# 1_interface.net
KiCad netlist of a schematic drawn in Altium Designer
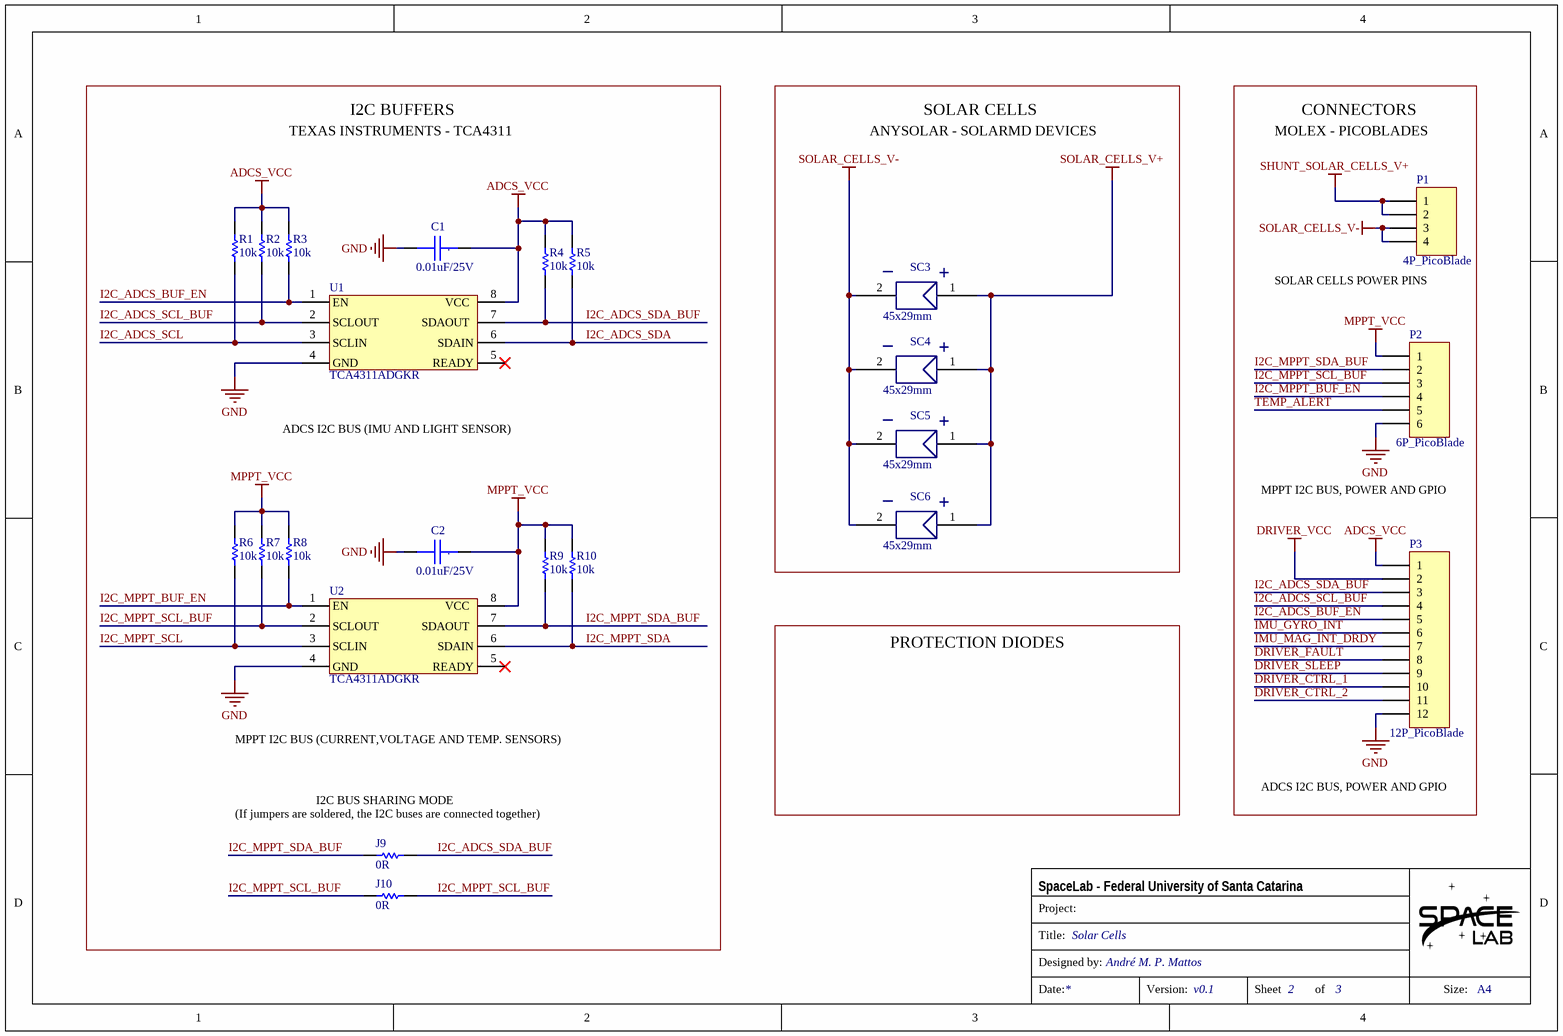
[diagram p0: 1_interface.schdoc]

(export (version "E")
  (design (tool "Eeschema 10.0.6"))
  (components
    (comp (ref "C1")
      (value "0.01uF/25V")
      (footprint "CC0805")
      (description "CAP CER 0.01uF 25V 10% X7R 0805")
      (fields (field (name "PARTNUMBER") "CL21B103KAANNNC"))
      (libsource (lib "schematics_library_legacy") (part "Cap_Cer_X7R_0.01uF_50V_0805"))
    )
    (comp (ref "C2")
      (value "0.01uF/25V")
      (footprint "CC0805")
      (description "CAP CER 0.01uF 25V 10% X7R 0805")
      (fields (field (name "PARTNUMBER") "CL21B103KAANNNC"))
      (libsource (lib "schematics_library_legacy") (part "Cap_Cer_X7R_0.01uF_50V_0805"))
    )
    (comp (ref "J9")
      (value "0R")
      (footprint "0805")
      (description "RES 0R OHM 1/16W JUMPER 0805")
      (fields (field (name "PARTNUMBER") "CRCW08050000Z0EA"))
      (libsource (lib "schematics_library_legacy") (part "R0R_JUMPER_1/16W_0805"))
    )
    (comp (ref "J10")
      (value "0R")
      (footprint "0805")
      (description "RES 0R OHM 1/16W JUMPER 0805")
      (fields (field (name "PARTNUMBER") "CRCW08050000Z0EA"))
      (libsource (lib "schematics_library_legacy") (part "R0R_JUMPER_1/16W_0805"))
    )
    (comp (ref "P1")
      (value "4P_PicoBlade")
      (footprint "HDR4 PicoBlade")
      (description "Header, 4-Pin")
      (fields
        (field (name "PARTNUMBER") "53398-0471")
        (field (name "MANUFACTURER") "Molex")
        (field (name "PUBLISHER") "Altium Limited")
      )
      (libsource (lib "schematics_library_legacy") (part "Header 4_PicoBlade"))
    )
    (comp (ref "P2")
      (value "6P_PicoBlade")
      (footprint "HDR6 PicoBlade")
      (description "Header, 6-Pin, Right Angle")
      (fields (field (name "PARTNUMBER") "53398-0671") (field (name "PUBLISHER") "Altium Limited"))
      (libsource (lib "schematics_library_legacy") (part "Header 6H_PicoBlade"))
    )
    (comp (ref "P3")
      (value "12P_PicoBlade")
      (footprint "HDR12 PicoBlade - duplicate")
      (description "Header, 12-Pin")
      (fields (field (name "PARTNUMBER") "53398-1271") (field (name "PUBLISHER") "Altium Limited"))
      (libsource (lib "schematics_library_legacy") (part "Header 12_PicoBlade"))
    )
    (comp (ref "R1")
      (value "10k")
      (footprint "0805")
      (description "RES 10K OHM 1/8W 1%  0805")
      (fields (field (name "PARTNUMBER") "CRCW080510K0FKEA"))
      (libsource (lib "schematics_library_legacy") (part "R10k_1%_1/8W_0805"))
    )
    (comp (ref "R2")
      (value "10k")
      (footprint "0805")
      (description "RES 10K OHM 1/8W 1%  0805")
      (fields (field (name "PARTNUMBER") "CRCW080510K0FKEA"))
      (libsource (lib "schematics_library_legacy") (part "R10k_1%_1/8W_0805"))
    )
    (comp (ref "R3")
      (value "10k")
      (footprint "0805")
      (description "RES 10K OHM 1/8W 1%  0805")
      (fields (field (name "PARTNUMBER") "CRCW080510K0FKEA"))
      (libsource (lib "schematics_library_legacy") (part "R10k_1%_1/8W_0805"))
    )
    (comp (ref "R4")
      (value "10k")
      (footprint "0805")
      (description "RES 10K OHM 1/8W 1%  0805")
      (fields (field (name "PARTNUMBER") "CRCW080510K0FKEA"))
      (libsource (lib "schematics_library_legacy") (part "R10k_1%_1/8W_0805"))
    )
    (comp (ref "R5")
      (value "10k")
      (footprint "0805")
      (description "RES 10K OHM 1/8W 1%  0805")
      (fields (field (name "PARTNUMBER") "CRCW080510K0FKEA"))
      (libsource (lib "schematics_library_legacy") (part "R10k_1%_1/8W_0805"))
    )
    (comp (ref "R6")
      (value "10k")
      (footprint "0805")
      (description "RES 10K OHM 1/8W 1%  0805")
      (fields (field (name "PARTNUMBER") "CRCW080510K0FKEA"))
      (libsource (lib "schematics_library_legacy") (part "R10k_1%_1/8W_0805"))
    )
    (comp (ref "R7")
      (value "10k")
      (footprint "0805")
      (description "RES 10K OHM 1/8W 1%  0805")
      (fields (field (name "PARTNUMBER") "CRCW080510K0FKEA"))
      (libsource (lib "schematics_library_legacy") (part "R10k_1%_1/8W_0805"))
    )
    (comp (ref "R8")
      (value "10k")
      (footprint "0805")
      (description "RES 10K OHM 1/8W 1%  0805")
      (fields (field (name "PARTNUMBER") "CRCW080510K0FKEA"))
      (libsource (lib "schematics_library_legacy") (part "R10k_1%_1/8W_0805"))
    )
    (comp (ref "R9")
      (value "10k")
      (footprint "0805")
      (description "RES 10K OHM 1/8W 1%  0805")
      (fields (field (name "PARTNUMBER") "CRCW080510K0FKEA"))
      (libsource (lib "schematics_library_legacy") (part "R10k_1%_1/8W_0805"))
    )
    (comp (ref "R10")
      (value "10k")
      (footprint "0805")
      (description "RES 10K OHM 1/8W 1%  0805")
      (fields (field (name "PARTNUMBER") "CRCW080510K0FKEA"))
      (libsource (lib "schematics_library_legacy") (part "R10k_1%_1/8W_0805"))
    )
    (comp (ref "SC3")
      (value "SC")
      (footprint "45x29mm_cell")
      (description "sm141k08lv")
      (fields (field (name "SIZE") "45x29mm"))
      (libsource (lib "schematics_library_legacy") (part "solar_cell_sm141k08lv"))
    )
    (comp (ref "SC4")
      (value "SC")
      (footprint "45x29mm_cell")
      (description "sm141k08lv")
      (fields (field (name "SIZE") "45x29mm"))
      (libsource (lib "schematics_library_legacy") (part "solar_cell_sm141k08lv"))
    )
    (comp (ref "SC5")
      (value "SC")
      (footprint "45x29mm_cell")
      (description "sm141k08lv")
      (fields (field (name "SIZE") "45x29mm"))
      (libsource (lib "schematics_library_legacy") (part "solar_cell_sm141k08lv"))
    )
    (comp (ref "SC6")
      (value "SC")
      (footprint "45x29mm_cell")
      (description "sm141k08lv")
      (fields (field (name "SIZE") "45x29mm"))
      (libsource (lib "schematics_library_legacy") (part "solar_cell_sm141k08lv"))
    )
    (comp (ref "U1")
      (value "TCA4311ADGKR")
      (footprint "DGK8")
      (description "IC SIGNAL BUFFER I2C VSSOP-8")
      (libsource (lib "schematics_library_legacy") (part "TCA4311ADGKR"))
    )
    (comp (ref "U2")
      (value "TCA4311ADGKR")
      (footprint "DGK8")
      (description "IC SIGNAL BUFFER I2C VSSOP-8")
      (libsource (lib "schematics_library_legacy") (part "TCA4311ADGKR"))
    )
  )
  (nets
    (net (code "1") (name "/DRIVER_CTRL_1") (class "Default")
      (node (ref "P3") (pin "10") (pinfunction "10_10") (pintype "passive"))
    )
    (net (code "2") (name "/DRIVER_CTRL_2") (class "Default")
      (node (ref "P3") (pin "11") (pinfunction "11_11") (pintype "passive"))
    )
    (net (code "3") (name "/DRIVER_FAULT") (class "Default")
      (node (ref "P3") (pin "8") (pinfunction "8_8") (pintype "passive"))
    )
    (net (code "4") (name "/DRIVER_SLEEP") (class "Default")
      (node (ref "P3") (pin "9") (pinfunction "9_9") (pintype "passive"))
    )
    (net (code "5") (name "/I2C_ADCS_BUF_EN") (class "Default")
      (node (ref "P3") (pin "5") (pinfunction "5_5") (pintype "passive"))
      (node (ref "R3") (pin "1") (pinfunction "1_1") (pintype "passive"))
      (node (ref "U1") (pin "1") (pinfunction "EN_1") (pintype "passive"))
    )
    (net (code "6") (name "/I2C_ADCS_SCL") (class "Default")
      (node (ref "R1") (pin "1") (pinfunction "1_1") (pintype "passive"))
      (node (ref "U1") (pin "3") (pinfunction "SCLIN_3") (pintype "passive"))
    )
    (net (code "7") (name "/I2C_ADCS_SCL_BUF") (class "Default")
      (node (ref "P3") (pin "4") (pinfunction "4_4") (pintype "passive"))
      (node (ref "R2") (pin "1") (pinfunction "1_1") (pintype "passive"))
      (node (ref "U1") (pin "2") (pinfunction "SCLOUT_2") (pintype "passive"))
    )
    (net (code "8") (name "/I2C_ADCS_SDA") (class "Default")
      (node (ref "R5") (pin "1") (pinfunction "1_1") (pintype "passive"))
      (node (ref "U1") (pin "6") (pinfunction "SDAIN_6") (pintype "passive"))
    )
    (net (code "9") (name "/I2C_ADCS_SDA_BUF") (class "Default")
      (node (ref "J9") (pin "1") (pinfunction "1_1") (pintype "passive"))
      (node (ref "P3") (pin "3") (pinfunction "3_3") (pintype "passive"))
      (node (ref "R4") (pin "1") (pinfunction "1_1") (pintype "passive"))
      (node (ref "U1") (pin "7") (pinfunction "SDAOUT_7") (pintype "passive"))
    )
    (net (code "10") (name "/I2C_MPPT_BUF_EN") (class "Default")
      (node (ref "P2") (pin "4") (pinfunction "4_4") (pintype "passive"))
      (node (ref "R8") (pin "1") (pinfunction "1_1") (pintype "passive"))
      (node (ref "U2") (pin "1") (pinfunction "EN_1") (pintype "passive"))
    )
    (net (code "11") (name "/I2C_MPPT_SCL") (class "Default")
      (node (ref "R6") (pin "1") (pinfunction "1_1") (pintype "passive"))
      (node (ref "U2") (pin "3") (pinfunction "SCLIN_3") (pintype "passive"))
    )
    (net (code "12") (name "/I2C_MPPT_SCL_BUF") (class "Default")
      (node (ref "J10") (pin "1") (pinfunction "1_1") (pintype "passive"))
      (node (ref "J10") (pin "2") (pinfunction "2_2") (pintype "passive"))
      (node (ref "P2") (pin "3") (pinfunction "3_3") (pintype "passive"))
      (node (ref "R7") (pin "1") (pinfunction "1_1") (pintype "passive"))
      (node (ref "U2") (pin "2") (pinfunction "SCLOUT_2") (pintype "passive"))
    )
    (net (code "13") (name "/I2C_MPPT_SDA") (class "Default")
      (node (ref "R10") (pin "1") (pinfunction "1_1") (pintype "passive"))
      (node (ref "U2") (pin "6") (pinfunction "SDAIN_6") (pintype "passive"))
    )
    (net (code "14") (name "/I2C_MPPT_SDA_BUF") (class "Default")
      (node (ref "J9") (pin "2") (pinfunction "2_2") (pintype "passive"))
      (node (ref "P2") (pin "2") (pinfunction "2_2") (pintype "passive"))
      (node (ref "R9") (pin "1") (pinfunction "1_1") (pintype "passive"))
      (node (ref "U2") (pin "7") (pinfunction "SDAOUT_7") (pintype "passive"))
    )
    (net (code "15") (name "/IMU_GYRO_INT") (class "Default")
      (node (ref "P3") (pin "6") (pinfunction "6_6") (pintype "passive"))
    )
    (net (code "16") (name "/IMU_MAG_INT_DRDY") (class "Default")
      (node (ref "P3") (pin "7") (pinfunction "7_7") (pintype "passive"))
    )
    (net (code "17") (name "/TEMP_ALERT") (class "Default")
      (node (ref "P2") (pin "5") (pinfunction "5_5") (pintype "passive"))
    )
    (net (code "18") (name "ADCS_VCC") (class "Default")
      (node (ref "C1") (pin "1") (pinfunction "1_1") (pintype "passive"))
      (node (ref "P3") (pin "1") (pinfunction "1_1") (pintype "passive"))
      (node (ref "R1") (pin "2") (pinfunction "2_2") (pintype "passive"))
      (node (ref "R2") (pin "2") (pinfunction "2_2") (pintype "passive"))
      (node (ref "R3") (pin "2") (pinfunction "2_2") (pintype "passive"))
      (node (ref "R4") (pin "2") (pinfunction "2_2") (pintype "passive"))
      (node (ref "R5") (pin "2") (pinfunction "2_2") (pintype "passive"))
      (node (ref "U1") (pin "8") (pinfunction "VCC_8") (pintype "power_in"))
    )
    (net (code "19") (name "DRIVER_VCC") (class "Default")
      (node (ref "P3") (pin "2") (pinfunction "2_2") (pintype "passive"))
    )
    (net (code "20") (name "GND") (class "Default")
      (node (ref "C1") (pin "2") (pinfunction "2_2") (pintype "passive"))
      (node (ref "C2") (pin "2") (pinfunction "2_2") (pintype "passive"))
      (node (ref "P2") (pin "6") (pinfunction "6_6") (pintype "passive"))
      (node (ref "P3") (pin "12") (pinfunction "12_12") (pintype "passive"))
      (node (ref "U1") (pin "4") (pinfunction "GND_4") (pintype "passive"))
      (node (ref "U2") (pin "4") (pinfunction "GND_4") (pintype "passive"))
    )
    (net (code "21") (name "MPPT_VCC") (class "Default")
      (node (ref "C2") (pin "1") (pinfunction "1_1") (pintype "passive"))
      (node (ref "P2") (pin "1") (pinfunction "1_1") (pintype "passive"))
      (node (ref "R10") (pin "2") (pinfunction "2_2") (pintype "passive"))
      (node (ref "R6") (pin "2") (pinfunction "2_2") (pintype "passive"))
      (node (ref "R7") (pin "2") (pinfunction "2_2") (pintype "passive"))
      (node (ref "R8") (pin "2") (pinfunction "2_2") (pintype "passive"))
      (node (ref "R9") (pin "2") (pinfunction "2_2") (pintype "passive"))
      (node (ref "U2") (pin "8") (pinfunction "VCC_8") (pintype "power_in"))
    )
    (net (code "22") (name "SHUNT_SOLAR_CELLS_V+") (class "Default")
      (node (ref "P1") (pin "1") (pinfunction "1_1") (pintype "passive"))
      (node (ref "P1") (pin "2") (pinfunction "2_2") (pintype "passive"))
    )
    (net (code "23") (name "SOLAR_CELLS_V+") (class "Default")
      (node (ref "SC3") (pin "1") (pinfunction "V+_1") (pintype "power_in"))
      (node (ref "SC4") (pin "1") (pinfunction "V+_1") (pintype "power_in"))
      (node (ref "SC5") (pin "1") (pinfunction "V+_1") (pintype "power_in"))
      (node (ref "SC6") (pin "1") (pinfunction "V+_1") (pintype "power_in"))
    )
    (net (code "24") (name "SOLAR_CELLS_V-") (class "Default")
      (node (ref "P1") (pin "3") (pinfunction "3_3") (pintype "passive"))
      (node (ref "P1") (pin "4") (pinfunction "4_4") (pintype "passive"))
      (node (ref "SC3") (pin "2") (pinfunction "V-_2") (pintype "power_in"))
      (node (ref "SC4") (pin "2") (pinfunction "V-_2") (pintype "power_in"))
      (node (ref "SC5") (pin "2") (pinfunction "V-_2") (pintype "power_in"))
      (node (ref "SC6") (pin "2") (pinfunction "V-_2") (pintype "power_in"))
    )
    (net (code "25") (name "unconnected-(U1-READY-Pad5)") (class "Default")
      (node (ref "U1") (pin "5") (pinfunction "READY_5") (pintype "passive+no_connect"))
    )
    (net (code "26") (name "unconnected-(U2-READY-Pad5)") (class "Default")
      (node (ref "U2") (pin "5") (pinfunction "READY_5") (pintype "passive+no_connect"))
    )
  )
)
